# esquema.net
KiCad netlist of a schematic drawn in Altium Designer
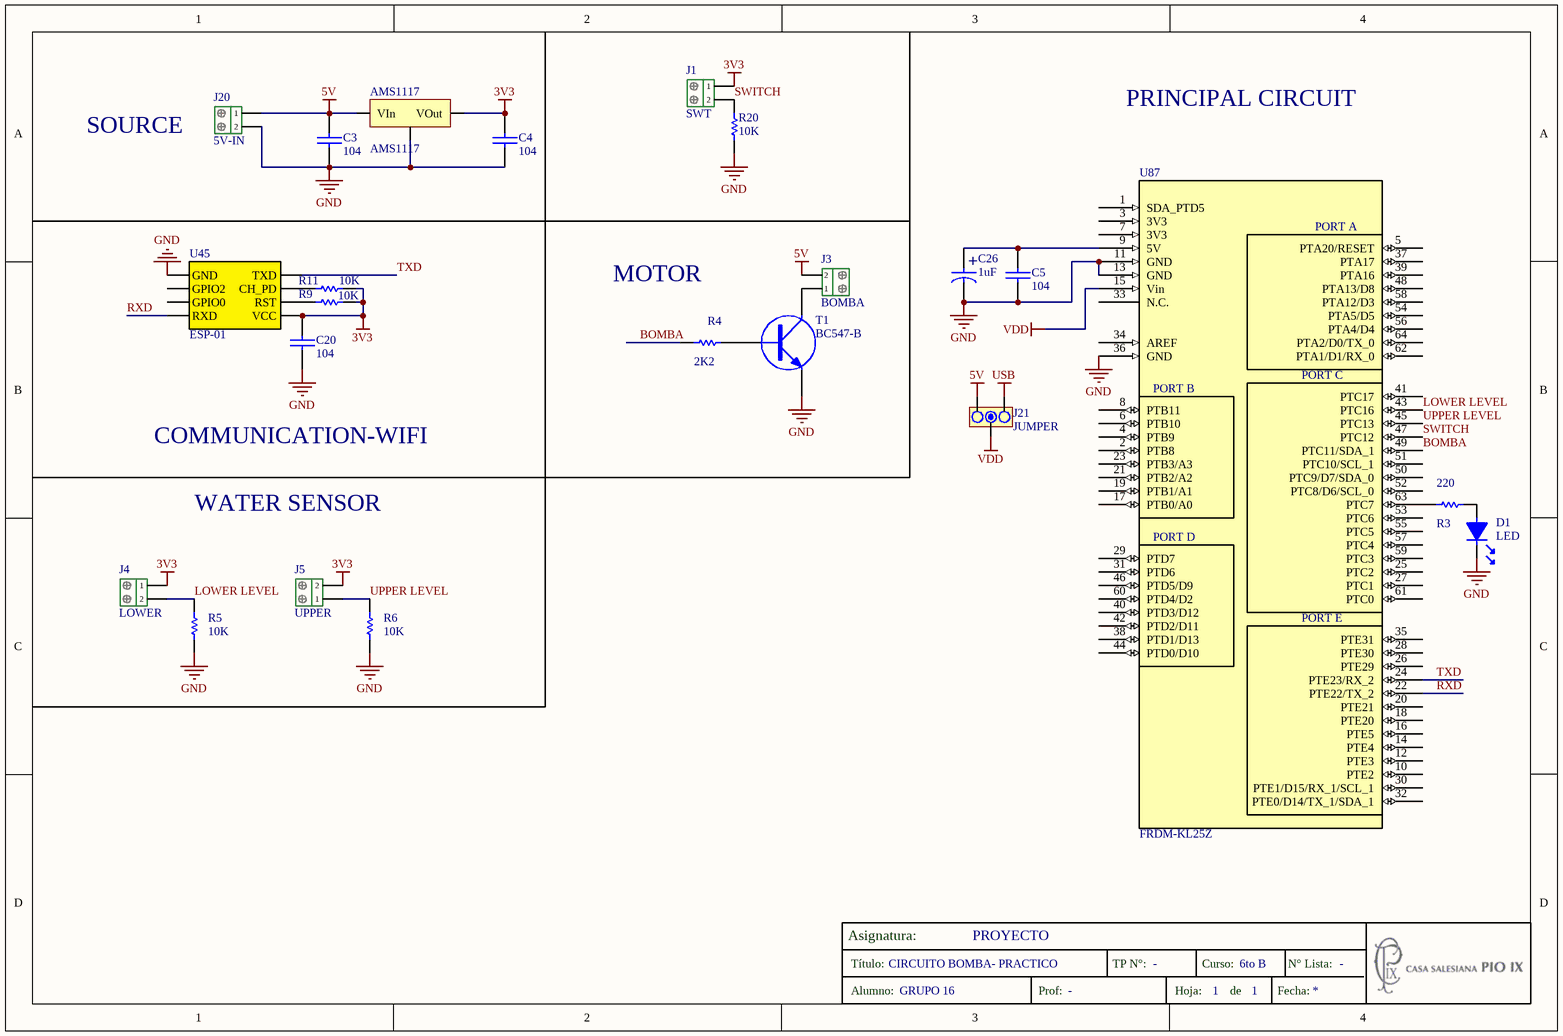
[diagram p0: esquema.SchDoc]

(export (version "E")
  (design (tool "Eeschema 10.0.6"))
  (components
    (comp (ref "AMS1117")
      (value "AMS1117")
      (footprint "AMS1117")
      (libsource (lib "Schlib1") (part "AMS1117"))
    )
    (comp (ref "C3")
      (value "104")
      (footprint "1206")
      (description "cap")
      (fields (field (name "AUTOR") "Guido Spataro"))
      (libsource (lib "Schlib1") (part "CAP"))
    )
    (comp (ref "C4")
      (value "104")
      (footprint "0805")
      (description "cap")
      (fields (field (name "AUTOR") "Guido Spataro"))
      (libsource (lib "Schlib1") (part "CAP"))
    )
    (comp (ref "C5")
      (value "104")
      (footprint "0805")
      (description "cap")
      (fields (field (name "AUTOR") "Guido Spataro"))
      (libsource (lib "scdlib") (part "CAP"))
    )
    (comp (ref "C20")
      (value "104")
      (footprint "0805")
      (description "cap")
      (fields (field (name "AUTOR") "Guido Spataro"))
      (libsource (lib "Schlib1") (part "CAP"))
    )
    (comp (ref "C26")
      (value "1uF")
      (footprint "CAP100RP")
      (description "Cap polarizado")
      (libsource (lib "Schlib1") (part "CAPPOL"))
    )
    (comp (ref "D1") (value "LED") (footprint "LED5") (libsource (lib "Schlib1") (part "LED")))
    (comp (ref "J1")
      (value "SWT")
      (footprint "BORNERA2")
      (description "Bornera de 2 pines")
      (fields (field (name "AUTOR") "Guido Spataro"))
      (libsource (lib "Schlib1") (part "Bornera_2"))
    )
    (comp (ref "J3")
      (value "BOMBA")
      (footprint "BORNERA2")
      (description "Bornera de 2 pines")
      (fields (field (name "AUTOR") "Guido Spataro"))
      (libsource (lib "Schlib1") (part "Bornera_2"))
    )
    (comp (ref "J4")
      (value "LOWER")
      (footprint "BORNERA2")
      (description "Bornera de 2 pines")
      (fields (field (name "AUTOR") "Guido Spataro"))
      (libsource (lib "Schlib1") (part "Bornera_2"))
    )
    (comp (ref "J5")
      (value "UPPER")
      (footprint "BORNERA2")
      (description "Bornera de 2 pines")
      (fields (field (name "AUTOR") "Guido Spataro"))
      (libsource (lib "") (part "Bornera_2_1"))
    )
    (comp (ref "J20")
      (value "5V-IN")
      (footprint "BORNERA2")
      (description "Bornera de 2 pines")
      (fields (field (name "AUTOR") "Guido Spataro"))
      (libsource (lib "Schlib1") (part "Bornera_2"))
    )
    (comp (ref "J21") (value "JUMPER") (footprint "SIP3") (libsource (lib "Schlib1") (part "JUMPER3")))
    (comp (ref "R3")
      (value "220")
      (footprint "0805")
      (description "Resistencia")
      (fields (field (name "AUTOR") "Guido Spataro"))
      (libsource (lib "Schlib1") (part "RES"))
    )
    (comp (ref "R4")
      (value "2K2")
      (footprint "0805")
      (description "Resistencia")
      (fields (field (name "AUTOR") "Guido Spataro"))
      (libsource (lib "Schlib1") (part "RES"))
    )
    (comp (ref "R5")
      (value "10K")
      (footprint "0805")
      (description "Resistencia")
      (fields (field (name "AUTOR") "Guido Spataro"))
      (libsource (lib "Schlib1") (part "RES"))
    )
    (comp (ref "R6")
      (value "10K")
      (footprint "0805")
      (description "Resistencia")
      (fields (field (name "AUTOR") "Guido Spataro"))
      (libsource (lib "Schlib1") (part "RES"))
    )
    (comp (ref "R9")
      (value "10K")
      (footprint "0805")
      (description "Resistencia")
      (fields (field (name "AUTOR") "Guido Spataro"))
      (libsource (lib "scdlib") (part "RES"))
    )
    (comp (ref "R11")
      (value "10K")
      (footprint "0805")
      (description "Resistencia")
      (fields (field (name "AUTOR") "Guido Spataro"))
      (libsource (lib "scdlib") (part "RES"))
    )
    (comp (ref "R20")
      (value "10K")
      (footprint "0805")
      (description "Resistencia")
      (fields (field (name "AUTOR") "Guido Spataro"))
      (libsource (lib "Schlib1") (part "RES"))
    )
    (comp (ref "T1")
      (value "BC547-B")
      (footprint "SOT23")
      (libsource (lib "Schlib1") (part "TRANSISTOR NPN"))
    )
    (comp (ref "U45") (value "ESP-01") (footprint "ESP-01") (libsource (lib "scdlib") (part "ESP-01")))
    (comp (ref "U87")
      (value "FRDM-KL25Z")
      (footprint "MICRO")
      (fields (field (name "AUTOR") "Guido Spataro"))
      (libsource (lib "Schlib1") (part "FRDM-KL25Z"))
    )
  )
  (nets
    (net (code "1") (name "/BOMBA") (class "Default")
      (node (ref "R4") (pin "2") (pinfunction "2_2") (pintype "passive"))
      (node (ref "U87") (pin "49") (pinfunction "PTC11/SDA_1_49") (pintype "bidirectional"))
    )
    (net (code "2") (name "/LOWER LEVEL") (class "Default")
      (node (ref "J4") (pin "2") (pinfunction "2_2") (pintype "passive"))
      (node (ref "R5") (pin "2") (pinfunction "2_2") (pintype "passive"))
      (node (ref "U87") (pin "43") (pinfunction "PTC16_43") (pintype "bidirectional"))
    )
    (net (code "3") (name "/RXD") (class "Default")
      (node (ref "U45") (pin "4") (pinfunction "RXD_4") (pintype "passive"))
      (node (ref "U87") (pin "22") (pinfunction "PTE22/TX_2_22") (pintype "bidirectional"))
    )
    (net (code "4") (name "/SWITCH") (class "Default")
      (node (ref "J1") (pin "2") (pinfunction "2_2") (pintype "passive"))
      (node (ref "R20") (pin "1") (pinfunction "1_1") (pintype "passive"))
      (node (ref "U87") (pin "47") (pinfunction "PTC12_47") (pintype "bidirectional"))
    )
    (net (code "5") (name "/TXD") (class "Default")
      (node (ref "U45") (pin "5") (pinfunction "TXD_5") (pintype "passive"))
      (node (ref "U87") (pin "24") (pinfunction "PTE23/RX_2_24") (pintype "bidirectional"))
    )
    (net (code "6") (name "/UPPER LEVEL") (class "Default")
      (node (ref "J5") (pin "1") (pinfunction "1_1") (pintype "passive"))
      (node (ref "R6") (pin "2") (pinfunction "2_2") (pintype "passive"))
      (node (ref "U87") (pin "45") (pinfunction "PTC13_45") (pintype "bidirectional"))
    )
    (net (code "7") (name "3V3") (class "Default")
      (node (ref "AMS1117") (pin "3") (pinfunction "VOut_3") (pintype "passive"))
      (node (ref "C20") (pin "1") (pinfunction "1_1") (pintype "passive"))
      (node (ref "C4") (pin "1") (pinfunction "1_1") (pintype "passive"))
      (node (ref "J1") (pin "1") (pinfunction "1_1") (pintype "passive"))
      (node (ref "J4") (pin "1") (pinfunction "1_1") (pintype "passive"))
      (node (ref "J5") (pin "2") (pinfunction "2_2") (pintype "passive"))
      (node (ref "R11") (pin "1") (pinfunction "1_1") (pintype "passive"))
      (node (ref "R9") (pin "1") (pinfunction "1_1") (pintype "passive"))
      (node (ref "U45") (pin "8") (pinfunction "VCC_8") (pintype "passive"))
    )
    (net (code "8") (name "5V") (class "Default")
      (node (ref "AMS1117") (pin "1") (pinfunction "VIn_1") (pintype "passive"))
      (node (ref "C3") (pin "1") (pinfunction "1_1") (pintype "passive"))
      (node (ref "J20") (pin "1") (pinfunction "1_1") (pintype "passive"))
      (node (ref "J21") (pin "1") (pinfunction "1_1") (pintype "passive"))
      (node (ref "J3") (pin "2") (pinfunction "2_2") (pintype "passive"))
    )
    (net (code "9") (name "GND") (class "Default")
      (node (ref "AMS1117") (pin "2") (pinfunction "GND_2") (pintype "passive"))
      (node (ref "C20") (pin "2") (pinfunction "2_2") (pintype "passive"))
      (node (ref "C26") (pin "2") (pinfunction "2_2") (pintype "passive"))
      (node (ref "C3") (pin "2") (pinfunction "2_2") (pintype "passive"))
      (node (ref "C4") (pin "2") (pinfunction "2_2") (pintype "passive"))
      (node (ref "C5") (pin "1") (pinfunction "1_1") (pintype "passive"))
      (node (ref "D1") (pin "2") (pinfunction "2_2") (pintype "passive"))
      (node (ref "J20") (pin "2") (pinfunction "2_2") (pintype "passive"))
      (node (ref "R20") (pin "2") (pinfunction "2_2") (pintype "passive"))
      (node (ref "R5") (pin "1") (pinfunction "1_1") (pintype "passive"))
      (node (ref "R6") (pin "1") (pinfunction "1_1") (pintype "passive"))
      (node (ref "T1") (pin "3") (pinfunction "E_3") (pintype "passive"))
      (node (ref "U45") (pin "1") (pinfunction "GND_1") (pintype "passive"))
      (node (ref "U87") (pin "11") (pinfunction "GND_11") (pintype "input"))
      (node (ref "U87") (pin "13") (pinfunction "GND_13") (pintype "input"))
      (node (ref "U87") (pin "36") (pinfunction "GND_36") (pintype "input"))
    )
    (net (code "10") (name "Net-(D1-Pad1)") (class "Default")
      (node (ref "D1") (pin "1") (pinfunction "1_1") (pintype "passive"))
      (node (ref "R3") (pin "1") (pinfunction "1_1") (pintype "passive"))
    )
    (net (code "11") (name "Net-(T1-B)") (class "Default")
      (node (ref "R4") (pin "1") (pinfunction "1_1") (pintype "passive"))
      (node (ref "T1") (pin "1") (pinfunction "B_1") (pintype "passive"))
    )
    (net (code "12") (name "Net-(T1-C)") (class "Default")
      (node (ref "J3") (pin "1") (pinfunction "1_1") (pintype "passive"))
      (node (ref "T1") (pin "2") (pinfunction "C_2") (pintype "passive"))
    )
    (net (code "13") (name "Net-(U45-CH_PD)") (class "Default")
      (node (ref "R11") (pin "2") (pinfunction "2_2") (pintype "passive"))
      (node (ref "U45") (pin "6") (pinfunction "CH_PD_6") (pintype "passive"))
    )
    (net (code "14") (name "Net-(U45-RST)") (class "Default")
      (node (ref "R9") (pin "2") (pinfunction "2_2") (pintype "passive"))
      (node (ref "U45") (pin "7") (pinfunction "RST_7") (pintype "passive"))
    )
    (net (code "15") (name "Net-(U87-5V)") (class "Default")
      (node (ref "C26") (pin "1") (pinfunction "1_1") (pintype "passive"))
      (node (ref "C5") (pin "2") (pinfunction "2_2") (pintype "passive"))
      (node (ref "U87") (pin "9") (pinfunction "5V_9") (pintype "input"))
    )
    (net (code "16") (name "Net-(U87-PTC7)") (class "Default")
      (node (ref "R3") (pin "2") (pinfunction "2_2") (pintype "passive"))
      (node (ref "U87") (pin "63") (pinfunction "PTC7_63") (pintype "bidirectional"))
    )
    (net (code "17") (name "USB") (class "Default")
      (node (ref "J21") (pin "3") (pinfunction "3_3") (pintype "passive"))
    )
    (net (code "18") (name "VDD") (class "Default")
      (node (ref "J21") (pin "2") (pinfunction "2_2") (pintype "passive"))
      (node (ref "U87") (pin "15") (pinfunction "Vin_15") (pintype "input"))
    )
    (net (code "19") (name "unconnected-(U45-GPIO0-Pad3)") (class "Default")
      (node (ref "U45") (pin "3") (pinfunction "GPIO0_3") (pintype "passive"))
    )
    (net (code "20") (name "unconnected-(U45-GPIO2-Pad2)") (class "Default")
      (node (ref "U45") (pin "2") (pinfunction "GPIO2_2") (pintype "passive"))
    )
    (net (code "21") (name "unconnected-(U87-3V3-Pad3)") (class "Default")
      (node (ref "U87") (pin "3") (pinfunction "3V3_3") (pintype "input"))
    )
    (net (code "22") (name "unconnected-(U87-3V3-Pad7)") (class "Default")
      (node (ref "U87") (pin "7") (pinfunction "3V3_7") (pintype "input"))
    )
    (net (code "23") (name "unconnected-(U87-AREF-Pad34)") (class "Default")
      (node (ref "U87") (pin "34") (pinfunction "AREF_34") (pintype "input"))
    )
    (net (code "24") (name "unconnected-(U87-N.C.-Pad33)") (class "Default")
      (node (ref "U87") (pin "33") (pinfunction "N.C._33") (pintype "open_emitter"))
    )
    (net (code "25") (name "unconnected-(U87-PTA1{slash}D1{slash}RX_0-Pad62)") (class "Default")
      (node (ref "U87") (pin "62") (pinfunction "PTA1/D1/RX_0_62") (pintype "bidirectional"))
    )
    (net (code "26") (name "unconnected-(U87-PTA2{slash}D0{slash}TX_0-Pad64)") (class "Default")
      (node (ref "U87") (pin "64") (pinfunction "PTA2/D0/TX_0_64") (pintype "bidirectional"))
    )
    (net (code "27") (name "unconnected-(U87-PTA4{slash}D4-Pad56)") (class "Default")
      (node (ref "U87") (pin "56") (pinfunction "PTA4/D4_56") (pintype "bidirectional"))
    )
    (net (code "28") (name "unconnected-(U87-PTA5{slash}D5-Pad54)") (class "Default")
      (node (ref "U87") (pin "54") (pinfunction "PTA5/D5_54") (pintype "bidirectional"))
    )
    (net (code "29") (name "unconnected-(U87-PTA12{slash}D3-Pad58)") (class "Default")
      (node (ref "U87") (pin "58") (pinfunction "PTA12/D3_58") (pintype "bidirectional"))
    )
    (net (code "30") (name "unconnected-(U87-PTA13{slash}D8-Pad48)") (class "Default")
      (node (ref "U87") (pin "48") (pinfunction "PTA13/D8_48") (pintype "bidirectional"))
    )
    (net (code "31") (name "unconnected-(U87-PTA16-Pad39)") (class "Default")
      (node (ref "U87") (pin "39") (pinfunction "PTA16_39") (pintype "bidirectional"))
    )
    (net (code "32") (name "unconnected-(U87-PTA17-Pad37)") (class "Default")
      (node (ref "U87") (pin "37") (pinfunction "PTA17_37") (pintype "bidirectional"))
    )
    (net (code "33") (name "unconnected-(U87-PTA20{slash}RESET-Pad5)") (class "Default")
      (node (ref "U87") (pin "5") (pinfunction "PTA20/RESET_5") (pintype "bidirectional"))
    )
    (net (code "34") (name "unconnected-(U87-PTB0{slash}A0-Pad17)") (class "Default")
      (node (ref "U87") (pin "17") (pinfunction "PTB0/A0_17") (pintype "bidirectional"))
    )
    (net (code "35") (name "unconnected-(U87-PTB1{slash}A1-Pad19)") (class "Default")
      (node (ref "U87") (pin "19") (pinfunction "PTB1/A1_19") (pintype "bidirectional"))
    )
    (net (code "36") (name "unconnected-(U87-PTB2{slash}A2-Pad21)") (class "Default")
      (node (ref "U87") (pin "21") (pinfunction "PTB2/A2_21") (pintype "bidirectional"))
    )
    (net (code "37") (name "unconnected-(U87-PTB3{slash}A3-Pad23)") (class "Default")
      (node (ref "U87") (pin "23") (pinfunction "PTB3/A3_23") (pintype "bidirectional"))
    )
    (net (code "38") (name "unconnected-(U87-PTB8-Pad2)") (class "Default")
      (node (ref "U87") (pin "2") (pinfunction "PTB8_2") (pintype "bidirectional"))
    )
    (net (code "39") (name "unconnected-(U87-PTB9-Pad4)") (class "Default")
      (node (ref "U87") (pin "4") (pinfunction "PTB9_4") (pintype "bidirectional"))
    )
    (net (code "40") (name "unconnected-(U87-PTB10-Pad6)") (class "Default")
      (node (ref "U87") (pin "6") (pinfunction "PTB10_6") (pintype "bidirectional"))
    )
    (net (code "41") (name "unconnected-(U87-PTB11-Pad8)") (class "Default")
      (node (ref "U87") (pin "8") (pinfunction "PTB11_8") (pintype "bidirectional"))
    )
    (net (code "42") (name "unconnected-(U87-PTC0-Pad61)") (class "Default")
      (node (ref "U87") (pin "61") (pinfunction "PTC0_61") (pintype "bidirectional"))
    )
    (net (code "43") (name "unconnected-(U87-PTC1-Pad27)") (class "Default")
      (node (ref "U87") (pin "27") (pinfunction "PTC1_27") (pintype "bidirectional"))
    )
    (net (code "44") (name "unconnected-(U87-PTC2-Pad25)") (class "Default")
      (node (ref "U87") (pin "25") (pinfunction "PTC2_25") (pintype "bidirectional"))
    )
    (net (code "45") (name "unconnected-(U87-PTC3-Pad59)") (class "Default")
      (node (ref "U87") (pin "59") (pinfunction "PTC3_59") (pintype "bidirectional"))
    )
    (net (code "46") (name "unconnected-(U87-PTC4-Pad57)") (class "Default")
      (node (ref "U87") (pin "57") (pinfunction "PTC4_57") (pintype "bidirectional"))
    )
    (net (code "47") (name "unconnected-(U87-PTC5-Pad55)") (class "Default")
      (node (ref "U87") (pin "55") (pinfunction "PTC5_55") (pintype "bidirectional"))
    )
    (net (code "48") (name "unconnected-(U87-PTC6-Pad53)") (class "Default")
      (node (ref "U87") (pin "53") (pinfunction "PTC6_53") (pintype "bidirectional"))
    )
    (net (code "49") (name "unconnected-(U87-PTC8{slash}D6{slash}SCL_0-Pad52)") (class "Default")
      (node (ref "U87") (pin "52") (pinfunction "PTC8/D6/SCL_0_52") (pintype "bidirectional"))
    )
    (net (code "50") (name "unconnected-(U87-PTC9{slash}D7{slash}SDA_0-Pad50)") (class "Default")
      (node (ref "U87") (pin "50") (pinfunction "PTC9/D7/SDA_0_50") (pintype "bidirectional"))
    )
    (net (code "51") (name "unconnected-(U87-PTC10{slash}SCL_1-Pad51)") (class "Default")
      (node (ref "U87") (pin "51") (pinfunction "PTC10/SCL_1_51") (pintype "bidirectional"))
    )
    (net (code "52") (name "unconnected-(U87-PTC17-Pad41)") (class "Default")
      (node (ref "U87") (pin "41") (pinfunction "PTC17_41") (pintype "bidirectional"))
    )
    (net (code "53") (name "unconnected-(U87-PTD0{slash}D10-Pad44)") (class "Default")
      (node (ref "U87") (pin "44") (pinfunction "PTD0/D10_44") (pintype "bidirectional"))
    )
    (net (code "54") (name "unconnected-(U87-PTD1{slash}D13-Pad38)") (class "Default")
      (node (ref "U87") (pin "38") (pinfunction "PTD1/D13_38") (pintype "bidirectional"))
    )
    (net (code "55") (name "unconnected-(U87-PTD2{slash}D11-Pad42)") (class "Default")
      (node (ref "U87") (pin "42") (pinfunction "PTD2/D11_42") (pintype "bidirectional"))
    )
    (net (code "56") (name "unconnected-(U87-PTD3{slash}D12-Pad40)") (class "Default")
      (node (ref "U87") (pin "40") (pinfunction "PTD3/D12_40") (pintype "bidirectional"))
    )
    (net (code "57") (name "unconnected-(U87-PTD4{slash}D2-Pad60)") (class "Default")
      (node (ref "U87") (pin "60") (pinfunction "PTD4/D2_60") (pintype "bidirectional"))
    )
    (net (code "58") (name "unconnected-(U87-PTD5{slash}D9-Pad46)") (class "Default")
      (node (ref "U87") (pin "46") (pinfunction "PTD5/D9_46") (pintype "bidirectional"))
    )
    (net (code "59") (name "unconnected-(U87-PTD6-Pad31)") (class "Default")
      (node (ref "U87") (pin "31") (pinfunction "PTD6_31") (pintype "bidirectional"))
    )
    (net (code "60") (name "unconnected-(U87-PTD7-Pad29)") (class "Default")
      (node (ref "U87") (pin "29") (pinfunction "PTD7_29") (pintype "bidirectional"))
    )
    (net (code "61") (name "unconnected-(U87-PTE0{slash}D14{slash}TX_1{slash}SDA_1-Pad32)") (class "Default")
      (node (ref "U87") (pin "32") (pinfunction "PTE0/D14/TX_1/SDA_1_32") (pintype "bidirectional"))
    )
    (net (code "62") (name "unconnected-(U87-PTE1{slash}D15{slash}RX_1{slash}SCL_1-Pad30)") (class "Default")
      (node (ref "U87") (pin "30") (pinfunction "PTE1/D15/RX_1/SCL_1_30") (pintype "bidirectional"))
    )
    (net (code "63") (name "unconnected-(U87-PTE2-Pad10)") (class "Default")
      (node (ref "U87") (pin "10") (pinfunction "PTE2_10") (pintype "bidirectional"))
    )
    (net (code "64") (name "unconnected-(U87-PTE3-Pad12)") (class "Default")
      (node (ref "U87") (pin "12") (pinfunction "PTE3_12") (pintype "bidirectional"))
    )
    (net (code "65") (name "unconnected-(U87-PTE4-Pad14)") (class "Default")
      (node (ref "U87") (pin "14") (pinfunction "PTE4_14") (pintype "bidirectional"))
    )
    (net (code "66") (name "unconnected-(U87-PTE5-Pad16)") (class "Default")
      (node (ref "U87") (pin "16") (pinfunction "PTE5_16") (pintype "bidirectional"))
    )
    (net (code "67") (name "unconnected-(U87-PTE20-Pad18)") (class "Default")
      (node (ref "U87") (pin "18") (pinfunction "PTE20_18") (pintype "bidirectional"))
    )
    (net (code "68") (name "unconnected-(U87-PTE21-Pad20)") (class "Default")
      (node (ref "U87") (pin "20") (pinfunction "PTE21_20") (pintype "bidirectional"))
    )
    (net (code "69") (name "unconnected-(U87-PTE29-Pad26)") (class "Default")
      (node (ref "U87") (pin "26") (pinfunction "PTE29_26") (pintype "bidirectional"))
    )
    (net (code "70") (name "unconnected-(U87-PTE30-Pad28)") (class "Default")
      (node (ref "U87") (pin "28") (pinfunction "PTE30_28") (pintype "bidirectional"))
    )
    (net (code "71") (name "unconnected-(U87-PTE31-Pad35)") (class "Default")
      (node (ref "U87") (pin "35") (pinfunction "PTE31_35") (pintype "bidirectional"))
    )
    (net (code "72") (name "unconnected-(U87-SDA_PTD5-Pad1)") (class "Default")
      (node (ref "U87") (pin "1") (pinfunction "SDA_PTD5_1") (pintype "input"))
    )
  )
)
